# PDB_ESC_BEC.net
KiCad netlist of a schematic drawn in EAGLE
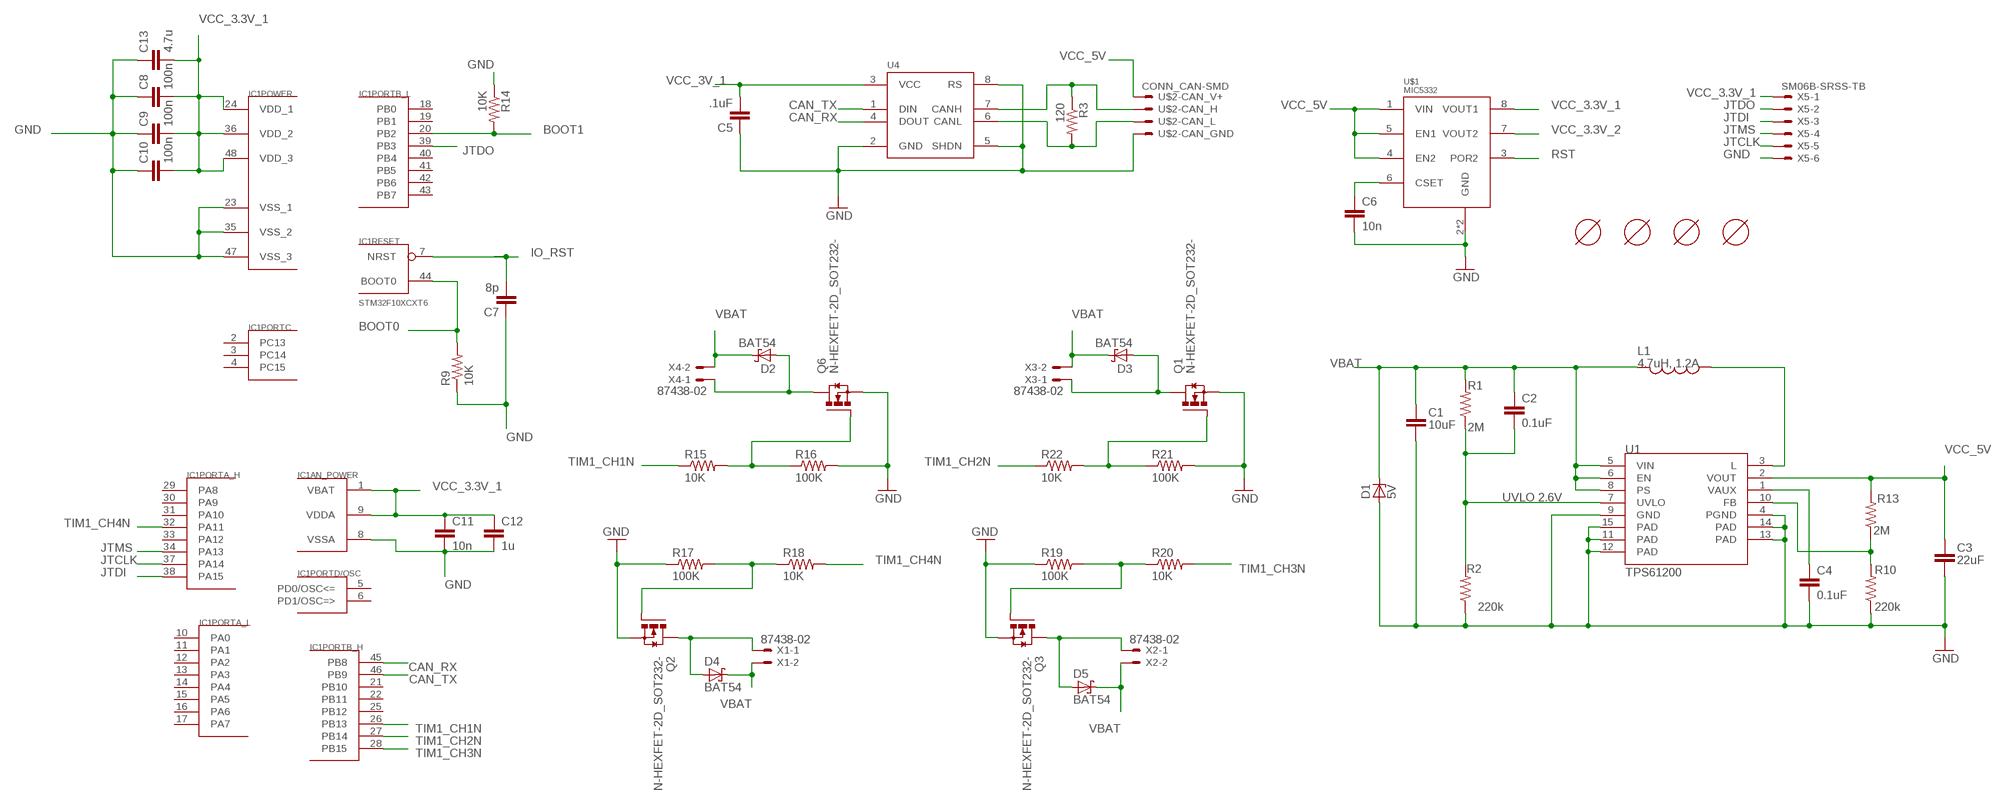
[diagram p0: schematic, sheet 1]

(export (version "E")
  (design (tool "Eeschema 10.0.6"))
  (components
    (comp (ref "C1")
      (value "10uF")
      (footprint "eagle-import:1206")
      (libsource (lib "eagle-import") (part "CAP1206"))
    )
    (comp (ref "C2")
      (value "0.1uF")
      (footprint "eagle-import:0603-CAP")
      (libsource (lib "eagle-import") (part "CAP0603-CAP"))
    )
    (comp (ref "C3")
      (value "22uF")
      (footprint "eagle-import:0805")
      (libsource (lib "eagle-import") (part "CAP0805"))
    )
    (comp (ref "C4")
      (value "0.1uF")
      (footprint "eagle-import:0603-CAP")
      (libsource (lib "eagle-import") (part "CAP0603-CAP"))
    )
    (comp (ref "C5")
      (value ".1uF")
      (footprint "eagle-import:C1206")
      (libsource (lib "eagle-import") (part "C-EUC1206"))
    )
    (comp (ref "C6")
      (value "10n")
      (footprint "eagle-import:0603-CAP")
      (libsource (lib "eagle-import") (part "CAP0603-CAP"))
    )
    (comp (ref "C7")
      (value "8p")
      (footprint "eagle-import:1206-CAP")
      (libsource (lib "eagle-import") (part "pixhawk2_CAP1206"))
    )
    (comp (ref "C8")
      (value "100n")
      (footprint "eagle-import:1206-CAP")
      (libsource (lib "eagle-import") (part "pixhawk2_CAP1206"))
    )
    (comp (ref "C9")
      (value "100n")
      (footprint "eagle-import:1206-CAP")
      (libsource (lib "eagle-import") (part "pixhawk2_CAP1206"))
    )
    (comp (ref "C10")
      (value "100n")
      (footprint "eagle-import:1206-CAP")
      (libsource (lib "eagle-import") (part "pixhawk2_CAP1206"))
    )
    (comp (ref "C11")
      (value "10n")
      (footprint "eagle-import:1206-CAP")
      (libsource (lib "eagle-import") (part "pixhawk2_CAP1206"))
    )
    (comp (ref "C12")
      (value "1u")
      (footprint "eagle-import:1206-CAP")
      (libsource (lib "eagle-import") (part "pixhawk2_CAP1206"))
    )
    (comp (ref "C13")
      (value "4.7u")
      (footprint "eagle-import:1206-CAP")
      (libsource (lib "eagle-import") (part "pixhawk2_CAP1206"))
    )
    (comp (ref "D1")
      (value "5V")
      (footprint "eagle-import:F126Z10")
      (libsource (lib "eagle-import") (part "ZENER-DIODEF126-10"))
    )
    (comp (ref "D2")
      (value "BAT54")
      (footprint "eagle-import:SOT23-3")
      (libsource (lib "eagle-import") (part "BAT54"))
    )
    (comp (ref "D3")
      (value "BAT54")
      (footprint "eagle-import:SOT23-3")
      (libsource (lib "eagle-import") (part "BAT54"))
    )
    (comp (ref "D4")
      (value "BAT54")
      (footprint "eagle-import:SOT23-3")
      (libsource (lib "eagle-import") (part "BAT54"))
    )
    (comp (ref "D5")
      (value "BAT54")
      (footprint "eagle-import:SOT23-3")
      (libsource (lib "eagle-import") (part "BAT54"))
    )
    (comp (ref "IC1")
      (value "STM32F10XCXT6")
      (footprint "eagle-import:TQFP48")
      (libsource (lib "eagle-import") (part "STM32F10XCXT6"))
    )
    (comp (ref "L1")
      (value "4.7uH, 1.2A")
      (footprint "eagle-import:CDRH2D09")
      (libsource (lib "eagle-import") (part "INDUCTOR."))
    )
    (comp (ref "Q1")
      (value "N-HEXFET-2D_SOT232-")
      (footprint "eagle-import:SOT223")
      (libsource (lib "eagle-import") (part "N-HEXFET-2D_?-SOT232"))
    )
    (comp (ref "Q2")
      (value "N-HEXFET-2D_SOT232-")
      (footprint "eagle-import:SOT223")
      (libsource (lib "eagle-import") (part "N-HEXFET-2D_?-SOT232"))
    )
    (comp (ref "Q3")
      (value "N-HEXFET-2D_SOT232-")
      (footprint "eagle-import:SOT223")
      (libsource (lib "eagle-import") (part "N-HEXFET-2D_?-SOT232"))
    )
    (comp (ref "Q6")
      (value "N-HEXFET-2D_SOT232-")
      (footprint "eagle-import:SOT223")
      (libsource (lib "eagle-import") (part "N-HEXFET-2D_?-SOT232"))
    )
    (comp (ref "R1")
      (value "2M")
      (footprint "eagle-import:0603-RES")
      (libsource (lib "eagle-import") (part "RESISTOR0603-RES"))
    )
    (comp (ref "R2")
      (value "220k")
      (footprint "eagle-import:0603-RES")
      (libsource (lib "eagle-import") (part "RESISTOR0603-RES"))
    )
    (comp (ref "R3")
      (value "120")
      (footprint "eagle-import:1206")
      (libsource (lib "eagle-import") (part "pixhawk2_RESISTOR1206"))
    )
    (comp (ref "R9")
      (value "10K")
      (footprint "eagle-import:1206")
      (libsource (lib "eagle-import") (part "pixhawk2_RESISTOR1206"))
    )
    (comp (ref "R10")
      (value "220k")
      (footprint "eagle-import:0603-RES")
      (libsource (lib "eagle-import") (part "RESISTOR0603-RES"))
    )
    (comp (ref "R13")
      (value "2M")
      (footprint "eagle-import:0603-RES")
      (libsource (lib "eagle-import") (part "RESISTOR0603-RES"))
    )
    (comp (ref "R14")
      (value "10K")
      (footprint "eagle-import:1206")
      (libsource (lib "eagle-import") (part "pixhawk2_RESISTOR1206"))
    )
    (comp (ref "R15")
      (value "10K")
      (footprint "eagle-import:1206")
      (libsource (lib "eagle-import") (part "pixhawk2_RESISTOR1206"))
    )
    (comp (ref "R16")
      (value "100K")
      (footprint "eagle-import:1206")
      (libsource (lib "eagle-import") (part "pixhawk2_RESISTOR1206"))
    )
    (comp (ref "R17")
      (value "100K")
      (footprint "eagle-import:1206")
      (libsource (lib "eagle-import") (part "pixhawk2_RESISTOR1206"))
    )
    (comp (ref "R18")
      (value "10K")
      (footprint "eagle-import:1206")
      (libsource (lib "eagle-import") (part "pixhawk2_RESISTOR1206"))
    )
    (comp (ref "R19")
      (value "100K")
      (footprint "eagle-import:1206")
      (libsource (lib "eagle-import") (part "pixhawk2_RESISTOR1206"))
    )
    (comp (ref "R20")
      (value "10K")
      (footprint "eagle-import:1206")
      (libsource (lib "eagle-import") (part "pixhawk2_RESISTOR1206"))
    )
    (comp (ref "R21")
      (value "100K")
      (footprint "eagle-import:1206")
      (libsource (lib "eagle-import") (part "pixhawk2_RESISTOR1206"))
    )
    (comp (ref "R22")
      (value "10K")
      (footprint "eagle-import:1206")
      (libsource (lib "eagle-import") (part "pixhawk2_RESISTOR1206"))
    )
    (comp (ref "U$1")
      (value "MIC5332")
      (footprint "eagle-import:MLF-8-EPAD")
      (libsource (lib "eagle-import") (part "MIC5332"))
    )
    (comp (ref "U$2")
      (value "CONN_CAN-SMD")
      (footprint "eagle-import:S4B-PH-SM4-TB")
      (libsource (lib "eagle-import") (part "CONN_CAN-SMD"))
    )
    (comp (ref "U$3")
      (value "MOUNT-HOLE3.1MM")
      (footprint "eagle-import:MOUNT-HOLE3.1")
      (libsource (lib "eagle-import") (part "MOUNT-HOLE3.1MM"))
    )
    (comp (ref "U$4")
      (value "MOUNT-HOLE3.1MM")
      (footprint "eagle-import:MOUNT-HOLE3.1")
      (libsource (lib "eagle-import") (part "MOUNT-HOLE3.1MM"))
    )
    (comp (ref "U$5")
      (value "MOUNT-HOLE3.1MM")
      (footprint "eagle-import:MOUNT-HOLE3.1")
      (libsource (lib "eagle-import") (part "MOUNT-HOLE3.1MM"))
    )
    (comp (ref "U$6")
      (value "MOUNT-HOLE3.1MM")
      (footprint "eagle-import:MOUNT-HOLE3.1")
      (libsource (lib "eagle-import") (part "MOUNT-HOLE3.1MM"))
    )
    (comp (ref "U1")
      (value "TPS61200")
      (footprint "eagle-import:QFN-10_PAD")
      (libsource (lib "eagle-import") (part "TPS61200"))
    )
    (comp (ref "U4")
      (value "MAX3051MAX3051ESA")
      (footprint "eagle-import:SO08")
      (libsource (lib "eagle-import") (part "MAX3051MAX3051ESA"))
    )
    (comp (ref "X1")
      (value "87438-02")
      (footprint "eagle-import:87438-02")
      (libsource (lib "eagle-import") (part "87438-02"))
    )
    (comp (ref "X2")
      (value "87438-02")
      (footprint "eagle-import:87438-02")
      (libsource (lib "eagle-import") (part "87438-02"))
    )
    (comp (ref "X3")
      (value "87438-02")
      (footprint "eagle-import:87438-02")
      (libsource (lib "eagle-import") (part "87438-02"))
    )
    (comp (ref "X4")
      (value "87438-02")
      (footprint "eagle-import:87438-02")
      (libsource (lib "eagle-import") (part "87438-02"))
    )
    (comp (ref "X5")
      (value "SM06B-SRSS-TB")
      (footprint "eagle-import:SM06B-SRSS-TB")
      (libsource (lib "eagle-import") (part "?M06B-SRSS-TBS"))
    )
  )
  (nets
    (net (code "1") (name "/BOOT0") (class "Default")
      (node (ref "IC1") (pin "44") (pinfunction "BOOT0_44") (pintype "input"))
      (node (ref "R9") (pin "2") (pinfunction "2_2") (pintype "passive"))
    )
    (net (code "2") (name "/BOOT1") (class "Default")
      (node (ref "IC1") (pin "20") (pinfunction "PB2_20") (pintype "bidirectional"))
      (node (ref "R14") (pin "2") (pinfunction "2_2") (pintype "passive"))
    )
    (net (code "3") (name "/CAN_RX") (class "Default")
      (node (ref "IC1") (pin "45") (pinfunction "PB8_45") (pintype "bidirectional"))
      (node (ref "U4") (pin "4") (pinfunction "DOUT_4") (pintype "output"))
    )
    (net (code "4") (name "/CAN_TX") (class "Default")
      (node (ref "IC1") (pin "46") (pinfunction "PB9_46") (pintype "bidirectional"))
      (node (ref "U4") (pin "1") (pinfunction "DIN_1") (pintype "input"))
    )
    (net (code "5") (name "/IO_RST") (class "Default")
      (node (ref "C7") (pin "P$2") (pinfunction "2_P$2") (pintype "passive"))
      (node (ref "IC1") (pin "7") (pinfunction "NRST_7") (pintype "input"))
    )
    (net (code "6") (name "/JTCLK") (class "Default")
      (node (ref "IC1") (pin "37") (pinfunction "PA14_37") (pintype "bidirectional"))
      (node (ref "X5") (pin "5") (pinfunction "S_5") (pintype "passive"))
    )
    (net (code "7") (name "/JTDI") (class "Default")
      (node (ref "IC1") (pin "38") (pinfunction "PA15_38") (pintype "bidirectional"))
      (node (ref "X5") (pin "3") (pinfunction "S_3") (pintype "passive"))
    )
    (net (code "8") (name "/JTDO") (class "Default")
      (node (ref "IC1") (pin "39") (pinfunction "PB3_39") (pintype "bidirectional"))
      (node (ref "X5") (pin "2") (pinfunction "S_2") (pintype "passive"))
    )
    (net (code "9") (name "/JTMS") (class "Default")
      (node (ref "IC1") (pin "34") (pinfunction "PA13_34") (pintype "bidirectional"))
      (node (ref "X5") (pin "4") (pinfunction "S_4") (pintype "passive"))
    )
    (net (code "10") (name "/RST") (class "Default")
      (node (ref "U$1") (pin "3") (pinfunction "POR2_3") (pintype "bidirectional"))
    )
    (net (code "11") (name "/TIM1_CH1N") (class "Default")
      (node (ref "IC1") (pin "26") (pinfunction "PB13_26") (pintype "bidirectional"))
      (node (ref "R15") (pin "1") (pinfunction "1_1") (pintype "passive"))
    )
    (net (code "12") (name "/TIM1_CH2N") (class "Default")
      (node (ref "IC1") (pin "27") (pinfunction "PB14_27") (pintype "bidirectional"))
      (node (ref "R22") (pin "1") (pinfunction "1_1") (pintype "passive"))
    )
    (net (code "13") (name "/TIM1_CH3N") (class "Default")
      (node (ref "IC1") (pin "28") (pinfunction "PB15_28") (pintype "bidirectional"))
      (node (ref "R20") (pin "2") (pinfunction "2_2") (pintype "passive"))
    )
    (net (code "14") (name "/TIM1_CH4N") (class "Default")
      (node (ref "IC1") (pin "32") (pinfunction "PA11_32") (pintype "bidirectional"))
      (node (ref "R18") (pin "2") (pinfunction "2_2") (pintype "passive"))
    )
    (net (code "15") (name "/VBAT") (class "Default")
      (node (ref "C1") (pin "1") (pinfunction "1_1") (pintype "passive"))
      (node (ref "C2") (pin "1") (pinfunction "1_1") (pintype "passive"))
      (node (ref "D1") (pin "C") (pinfunction "C_C") (pintype "passive"))
      (node (ref "D2") (pin "3") (pinfunction "C_3") (pintype "passive"))
      (node (ref "D3") (pin "3") (pinfunction "C_3") (pintype "passive"))
      (node (ref "D4") (pin "3") (pinfunction "C_3") (pintype "passive"))
      (node (ref "D5") (pin "3") (pinfunction "C_3") (pintype "passive"))
      (node (ref "L1") (pin "P$2") (pinfunction "2_P$2") (pintype "passive"))
      (node (ref "R1") (pin "2") (pinfunction "2_2") (pintype "passive"))
      (node (ref "U1") (pin "5") (pinfunction "VIN_5") (pintype "power_in"))
      (node (ref "U1") (pin "6") (pinfunction "EN_6") (pintype "input"))
      (node (ref "U1") (pin "8") (pinfunction "PS_8") (pintype "input"))
      (node (ref "X1") (pin "2") (pinfunction "S_2") (pintype "passive"))
      (node (ref "X2") (pin "2") (pinfunction "S_2") (pintype "passive"))
      (node (ref "X3") (pin "2") (pinfunction "S_2") (pintype "passive"))
      (node (ref "X4") (pin "2") (pinfunction "S_2") (pintype "passive"))
    )
    (net (code "16") (name "/VCC_3.3V_1") (class "Default")
      (node (ref "C10") (pin "P$2") (pinfunction "2_P$2") (pintype "passive"))
      (node (ref "C11") (pin "P$1") (pinfunction "1_P$1") (pintype "passive"))
      (node (ref "C12") (pin "P$1") (pinfunction "1_P$1") (pintype "passive"))
      (node (ref "C13") (pin "P$2") (pinfunction "2_P$2") (pintype "passive"))
      (node (ref "C8") (pin "P$2") (pinfunction "2_P$2") (pintype "passive"))
      (node (ref "C9") (pin "P$2") (pinfunction "2_P$2") (pintype "passive"))
      (node (ref "IC1") (pin "1") (pinfunction "VBAT_1") (pintype "power_in"))
      (node (ref "IC1") (pin "24") (pinfunction "VDD_1_24") (pintype "power_in"))
      (node (ref "IC1") (pin "36") (pinfunction "VDD_2_36") (pintype "power_in"))
      (node (ref "IC1") (pin "48") (pinfunction "VDD_3_48") (pintype "power_in"))
      (node (ref "IC1") (pin "9") (pinfunction "VDDA_9") (pintype "power_in"))
      (node (ref "U$1") (pin "8") (pinfunction "VOUT1_8") (pintype "bidirectional"))
      (node (ref "X5") (pin "1") (pinfunction "S_1") (pintype "passive"))
    )
    (net (code "17") (name "/VCC_3.3V_2") (class "Default")
      (node (ref "U$1") (pin "7") (pinfunction "VOUT2_7") (pintype "bidirectional"))
    )
    (net (code "18") (name "/VCC_3V_1") (class "Default")
      (node (ref "C5") (pin "2") (pinfunction "2_2") (pintype "passive"))
      (node (ref "U4") (pin "3") (pinfunction "VCC_3") (pintype "input"))
    )
    (net (code "19") (name "/VCC_5V") (class "Default")
      (node (ref "C3") (pin "1") (pinfunction "1_1") (pintype "passive"))
      (node (ref "R13") (pin "2") (pinfunction "2_2") (pintype "passive"))
      (node (ref "U$1") (pin "1") (pinfunction "VIN_1") (pintype "bidirectional"))
      (node (ref "U$1") (pin "4") (pinfunction "EN2_4") (pintype "bidirectional"))
      (node (ref "U$1") (pin "5") (pinfunction "EN1_5") (pintype "bidirectional"))
      (node (ref "U$2") (pin "1") (pinfunction "S_1") (pintype "passive"))
      (node (ref "U1") (pin "2") (pinfunction "VOUT_2") (pintype "passive"))
    )
    (net (code "20") (name "GND") (class "Default")
      (node (ref "C1") (pin "2") (pinfunction "2_2") (pintype "passive"))
      (node (ref "C10") (pin "P$1") (pinfunction "1_P$1") (pintype "passive"))
      (node (ref "C11") (pin "P$2") (pinfunction "2_P$2") (pintype "passive"))
      (node (ref "C12") (pin "P$2") (pinfunction "2_P$2") (pintype "passive"))
      (node (ref "C13") (pin "P$1") (pinfunction "1_P$1") (pintype "passive"))
      (node (ref "C3") (pin "2") (pinfunction "2_2") (pintype "passive"))
      (node (ref "C4") (pin "2") (pinfunction "2_2") (pintype "passive"))
      (node (ref "C5") (pin "1") (pinfunction "1_1") (pintype "passive"))
      (node (ref "C6") (pin "2") (pinfunction "2_2") (pintype "passive"))
      (node (ref "C7") (pin "P$1") (pinfunction "1_P$1") (pintype "passive"))
      (node (ref "C8") (pin "P$1") (pinfunction "1_P$1") (pintype "passive"))
      (node (ref "C9") (pin "P$1") (pinfunction "1_P$1") (pintype "passive"))
      (node (ref "D1") (pin "A") (pinfunction "A_A") (pintype "passive"))
      (node (ref "IC1") (pin "23") (pinfunction "VSS_1_23") (pintype "power_in"))
      (node (ref "IC1") (pin "35") (pinfunction "VSS_2_35") (pintype "power_in"))
      (node (ref "IC1") (pin "47") (pinfunction "VSS_3_47") (pintype "power_in"))
      (node (ref "IC1") (pin "8") (pinfunction "VSSA_8") (pintype "power_in"))
      (node (ref "Q1") (pin "3") (pinfunction "S_3") (pintype "passive"))
      (node (ref "Q2") (pin "3") (pinfunction "S_3") (pintype "passive"))
      (node (ref "Q3") (pin "3") (pinfunction "S_3") (pintype "passive"))
      (node (ref "Q6") (pin "3") (pinfunction "S_3") (pintype "passive"))
      (node (ref "R10") (pin "1") (pinfunction "1_1") (pintype "passive"))
      (node (ref "R14") (pin "1") (pinfunction "1_1") (pintype "passive"))
      (node (ref "R16") (pin "2") (pinfunction "2_2") (pintype "passive"))
      (node (ref "R17") (pin "1") (pinfunction "1_1") (pintype "passive"))
      (node (ref "R19") (pin "1") (pinfunction "1_1") (pintype "passive"))
      (node (ref "R2") (pin "1") (pinfunction "1_1") (pintype "passive"))
      (node (ref "R21") (pin "2") (pinfunction "2_2") (pintype "passive"))
      (node (ref "R9") (pin "1") (pinfunction "1_1") (pintype "passive"))
      (node (ref "U$1") (pin "2") (pinfunction "GND_2") (pintype "bidirectional"))
      (node (ref "U$1") (pin "GND") (pinfunction "GND_GND") (pintype "bidirectional"))
      (node (ref "U$2") (pin "4") (pinfunction "S_4") (pintype "passive"))
      (node (ref "U1") (pin "11") (pinfunction "PAD_11") (pintype "power_in"))
      (node (ref "U1") (pin "12") (pinfunction "PAD_12") (pintype "power_in"))
      (node (ref "U1") (pin "13") (pinfunction "PAD_13") (pintype "power_in"))
      (node (ref "U1") (pin "14") (pinfunction "PAD_14") (pintype "power_in"))
      (node (ref "U1") (pin "15") (pinfunction "PAD_15") (pintype "power_in"))
      (node (ref "U1") (pin "4") (pinfunction "PGND_4") (pintype "power_in"))
      (node (ref "U1") (pin "9") (pinfunction "GND_9") (pintype "power_in"))
      (node (ref "U4") (pin "2") (pinfunction "GND_2") (pintype "power_in"))
      (node (ref "U4") (pin "5") (pinfunction "SHDN_5") (pintype "input"))
      (node (ref "U4") (pin "8") (pinfunction "RS_8") (pintype "input"))
      (node (ref "X5") (pin "6") (pinfunction "S_6") (pintype "passive"))
    )
    (net (code "21") (name "Net-(D2-A)") (class "Default")
      (node (ref "D2") (pin "1") (pinfunction "A_1") (pintype "passive"))
      (node (ref "Q6") (pin "2") (pinfunction "D_2") (pintype "passive"))
      (node (ref "Q6") (pin "4") (pinfunction "D_4") (pintype "passive"))
      (node (ref "X4") (pin "1") (pinfunction "S_1") (pintype "passive"))
    )
    (net (code "22") (name "Net-(D3-A)") (class "Default")
      (node (ref "D3") (pin "1") (pinfunction "A_1") (pintype "passive"))
      (node (ref "Q1") (pin "2") (pinfunction "D_2") (pintype "passive"))
      (node (ref "Q1") (pin "4") (pinfunction "D_4") (pintype "passive"))
      (node (ref "X3") (pin "1") (pinfunction "S_1") (pintype "passive"))
    )
    (net (code "23") (name "Net-(D4-A)") (class "Default")
      (node (ref "D4") (pin "1") (pinfunction "A_1") (pintype "passive"))
      (node (ref "Q2") (pin "2") (pinfunction "D_2") (pintype "passive"))
      (node (ref "Q2") (pin "4") (pinfunction "D_4") (pintype "passive"))
      (node (ref "X1") (pin "1") (pinfunction "S_1") (pintype "passive"))
    )
    (net (code "24") (name "Net-(D5-A)") (class "Default")
      (node (ref "D5") (pin "1") (pinfunction "A_1") (pintype "passive"))
      (node (ref "Q3") (pin "2") (pinfunction "D_2") (pintype "passive"))
      (node (ref "Q3") (pin "4") (pinfunction "D_4") (pintype "passive"))
      (node (ref "X2") (pin "1") (pinfunction "S_1") (pintype "passive"))
    )
    (net (code "25") (name "Net-(L1-1)") (class "Default")
      (node (ref "L1") (pin "P$1") (pinfunction "1_P$1") (pintype "passive"))
      (node (ref "U1") (pin "3") (pinfunction "L_3") (pintype "passive"))
    )
    (net (code "26") (name "Net-(Q1-G)") (class "Default")
      (node (ref "Q1") (pin "1") (pinfunction "G_1") (pintype "passive"))
      (node (ref "R21") (pin "1") (pinfunction "1_1") (pintype "passive"))
      (node (ref "R22") (pin "2") (pinfunction "2_2") (pintype "passive"))
    )
    (net (code "27") (name "Net-(Q2-G)") (class "Default")
      (node (ref "Q2") (pin "1") (pinfunction "G_1") (pintype "passive"))
      (node (ref "R17") (pin "2") (pinfunction "2_2") (pintype "passive"))
      (node (ref "R18") (pin "1") (pinfunction "1_1") (pintype "passive"))
    )
    (net (code "28") (name "Net-(Q3-G)") (class "Default")
      (node (ref "Q3") (pin "1") (pinfunction "G_1") (pintype "passive"))
      (node (ref "R19") (pin "2") (pinfunction "2_2") (pintype "passive"))
      (node (ref "R20") (pin "1") (pinfunction "1_1") (pintype "passive"))
    )
    (net (code "29") (name "Net-(Q6-G)") (class "Default")
      (node (ref "Q6") (pin "1") (pinfunction "G_1") (pintype "passive"))
      (node (ref "R15") (pin "2") (pinfunction "2_2") (pintype "passive"))
      (node (ref "R16") (pin "1") (pinfunction "1_1") (pintype "passive"))
    )
    (net (code "30") (name "Net-(U$1-CSET)") (class "Default")
      (node (ref "C6") (pin "1") (pinfunction "1_1") (pintype "passive"))
      (node (ref "U$1") (pin "6") (pinfunction "CSET_6") (pintype "bidirectional"))
    )
    (net (code "31") (name "Net-(U$2B-S)") (class "Default")
      (node (ref "R3") (pin "1") (pinfunction "1_1") (pintype "passive"))
      (node (ref "U$2") (pin "2") (pinfunction "S_2") (pintype "passive"))
      (node (ref "U4") (pin "7") (pinfunction "CANH_7") (pintype "bidirectional"))
    )
    (net (code "32") (name "Net-(U$2C-S)") (class "Default")
      (node (ref "R3") (pin "2") (pinfunction "2_2") (pintype "passive"))
      (node (ref "U$2") (pin "3") (pinfunction "S_3") (pintype "passive"))
      (node (ref "U4") (pin "6") (pinfunction "CANL_6") (pintype "bidirectional"))
    )
    (net (code "33") (name "Net-(U1-FB)") (class "Default")
      (node (ref "R10") (pin "2") (pinfunction "2_2") (pintype "passive"))
      (node (ref "R13") (pin "1") (pinfunction "1_1") (pintype "passive"))
      (node (ref "U1") (pin "10") (pinfunction "FB_10") (pintype "passive"))
    )
    (net (code "34") (name "Net-(U1-UVLO)") (class "Default")
      (node (ref "C2") (pin "2") (pinfunction "2_2") (pintype "passive"))
      (node (ref "R1") (pin "1") (pinfunction "1_1") (pintype "passive"))
      (node (ref "R2") (pin "2") (pinfunction "2_2") (pintype "passive"))
      (node (ref "U1") (pin "7") (pinfunction "UVLO_7") (pintype "passive"))
    )
    (net (code "35") (name "Net-(U1-VAUX)") (class "Default")
      (node (ref "C4") (pin "1") (pinfunction "1_1") (pintype "passive"))
      (node (ref "U1") (pin "1") (pinfunction "VAUX_1") (pintype "passive"))
    )
    (net (code "36") (name "unconnected-(IC1B-PA8-Pad29)") (class "Default")
      (node (ref "IC1") (pin "29") (pinfunction "PA8_29") (pintype "bidirectional"))
    )
    (net (code "37") (name "unconnected-(IC1B-PA9-Pad30)") (class "Default")
      (node (ref "IC1") (pin "30") (pinfunction "PA9_30") (pintype "bidirectional"))
    )
    (net (code "38") (name "unconnected-(IC1B-PA10-Pad31)") (class "Default")
      (node (ref "IC1") (pin "31") (pinfunction "PA10_31") (pintype "bidirectional"))
    )
    (net (code "39") (name "unconnected-(IC1B-PA12-Pad33)") (class "Default")
      (node (ref "IC1") (pin "33") (pinfunction "PA12_33") (pintype "bidirectional"))
    )
    (net (code "40") (name "unconnected-(IC1C-PA0-Pad10)") (class "Default")
      (node (ref "IC1") (pin "10") (pinfunction "PA0_10") (pintype "bidirectional"))
    )
    (net (code "41") (name "unconnected-(IC1C-PA1-Pad11)") (class "Default")
      (node (ref "IC1") (pin "11") (pinfunction "PA1_11") (pintype "bidirectional"))
    )
    (net (code "42") (name "unconnected-(IC1C-PA2-Pad12)") (class "Default")
      (node (ref "IC1") (pin "12") (pinfunction "PA2_12") (pintype "bidirectional"))
    )
    (net (code "43") (name "unconnected-(IC1C-PA3-Pad13)") (class "Default")
      (node (ref "IC1") (pin "13") (pinfunction "PA3_13") (pintype "bidirectional"))
    )
    (net (code "44") (name "unconnected-(IC1C-PA4-Pad14)") (class "Default")
      (node (ref "IC1") (pin "14") (pinfunction "PA4_14") (pintype "bidirectional"))
    )
    (net (code "45") (name "unconnected-(IC1C-PA5-Pad15)") (class "Default")
      (node (ref "IC1") (pin "15") (pinfunction "PA5_15") (pintype "bidirectional"))
    )
    (net (code "46") (name "unconnected-(IC1C-PA6-Pad16)") (class "Default")
      (node (ref "IC1") (pin "16") (pinfunction "PA6_16") (pintype "bidirectional"))
    )
    (net (code "47") (name "unconnected-(IC1C-PA7-Pad17)") (class "Default")
      (node (ref "IC1") (pin "17") (pinfunction "PA7_17") (pintype "bidirectional"))
    )
    (net (code "48") (name "unconnected-(IC1D-PB10-Pad21)") (class "Default")
      (node (ref "IC1") (pin "21") (pinfunction "PB10_21") (pintype "bidirectional"))
    )
    (net (code "49") (name "unconnected-(IC1D-PB11-Pad22)") (class "Default")
      (node (ref "IC1") (pin "22") (pinfunction "PB11_22") (pintype "bidirectional"))
    )
    (net (code "50") (name "unconnected-(IC1D-PB12-Pad25)") (class "Default")
      (node (ref "IC1") (pin "25") (pinfunction "PB12_25") (pintype "bidirectional"))
    )
    (net (code "51") (name "unconnected-(IC1E-PB0-Pad18)") (class "Default")
      (node (ref "IC1") (pin "18") (pinfunction "PB0_18") (pintype "bidirectional"))
    )
    (net (code "52") (name "unconnected-(IC1E-PB1-Pad19)") (class "Default")
      (node (ref "IC1") (pin "19") (pinfunction "PB1_19") (pintype "bidirectional"))
    )
    (net (code "53") (name "unconnected-(IC1E-PB4-Pad40)") (class "Default")
      (node (ref "IC1") (pin "40") (pinfunction "PB4_40") (pintype "bidirectional"))
    )
    (net (code "54") (name "unconnected-(IC1E-PB5-Pad41)") (class "Default")
      (node (ref "IC1") (pin "41") (pinfunction "PB5_41") (pintype "bidirectional"))
    )
    (net (code "55") (name "unconnected-(IC1E-PB6-Pad42)") (class "Default")
      (node (ref "IC1") (pin "42") (pinfunction "PB6_42") (pintype "bidirectional"))
    )
    (net (code "56") (name "unconnected-(IC1E-PB7-Pad43)") (class "Default")
      (node (ref "IC1") (pin "43") (pinfunction "PB7_43") (pintype "bidirectional"))
    )
    (net (code "57") (name "unconnected-(IC1F-PC13-Pad2)") (class "Default")
      (node (ref "IC1") (pin "2") (pinfunction "PC13_2") (pintype "bidirectional"))
    )
    (net (code "58") (name "unconnected-(IC1F-PC14-Pad3)") (class "Default")
      (node (ref "IC1") (pin "3") (pinfunction "PC14_3") (pintype "bidirectional"))
    )
    (net (code "59") (name "unconnected-(IC1F-PC15-Pad4)") (class "Default")
      (node (ref "IC1") (pin "4") (pinfunction "PC15_4") (pintype "bidirectional"))
    )
    (net (code "60") (name "unconnected-(IC1G-PD0{slash}OSC<=-Pad5)") (class "Default")
      (node (ref "IC1") (pin "5") (pinfunction "PD0/OSC<=_5") (pintype "bidirectional"))
    )
    (net (code "61") (name "unconnected-(IC1G-PD1{slash}OSC=>-Pad6)") (class "Default")
      (node (ref "IC1") (pin "6") (pinfunction "PD1/OSC=>_6") (pintype "bidirectional"))
    )
  )
)
